# PWR_INP.net
KiCad netlist of a schematic drawn in Altium Designer
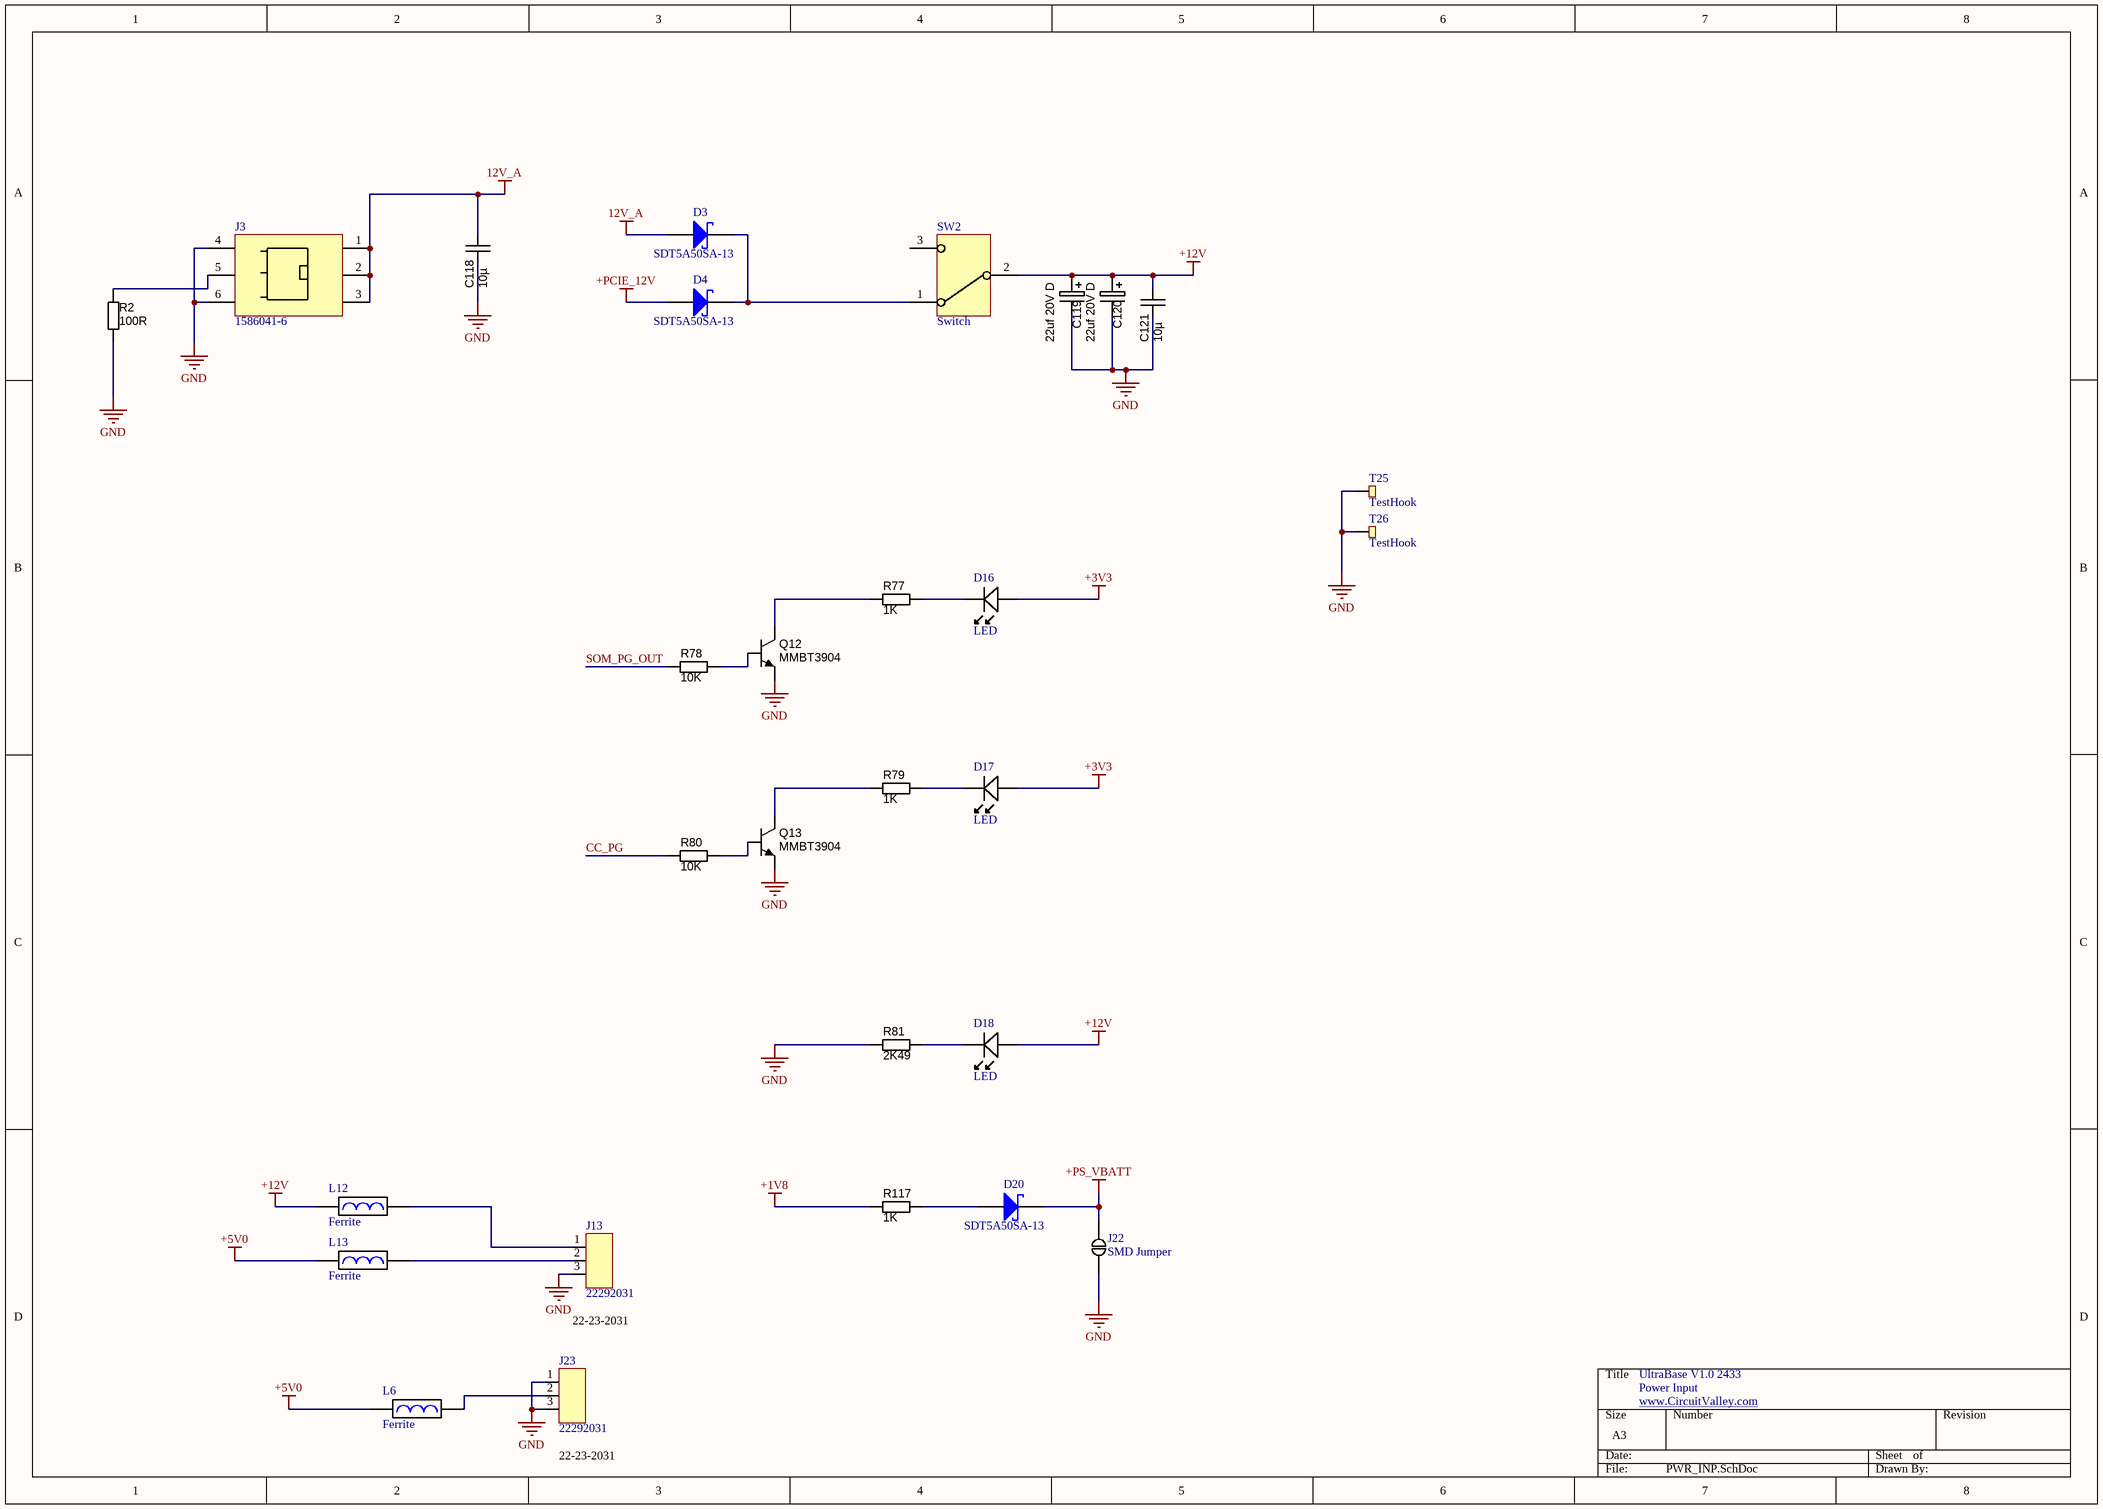
[diagram p0: PWR_INP.SchDoc]

(export (version "E")
  (design (tool "Eeschema 10.0.6"))
  (components
    (comp (ref "C118")
      (value "10µ")
      (footprint "CAPC3225N")
      (description "Capacitor SMD Cer 10uF 20% 16V X5R 1210")
      (fields (field (name "TOLERANCE") "±20%"))
      (libsource (lib "PBL - Capacitors") (part "CAPC_10u_1210_50V"))
    )
    (comp (ref "C119")
      (value "22uf 20V D")
      (footprint "CAPMP7343X310N")
      (description "Capacitor SMD Tant 330uF 20% 6V3 2917")
      (fields
        (field (name "TOLERANCE") "±20%")
        (field (name "MANUFACTURER PART NUMBER") "T520D337M006ATE015")
      )
      (libsource (lib "PBL - Capacitors") (part "CAPT_330u_2917_6V3"))
    )
    (comp (ref "C120")
      (value "22uf 20V D")
      (footprint "CAPMP7343X310N")
      (description "Capacitor SMD Tant 330uF 20% 6V3 2917")
      (fields
        (field (name "TOLERANCE") "±20%")
        (field (name "MANUFACTURER PART NUMBER") "T520D337M006ATE015")
      )
      (libsource (lib "PBL - Capacitors") (part "CAPT_330u_2917_6V3"))
    )
    (comp (ref "C121")
      (value "10µ")
      (footprint "CAPC3225N")
      (description "Capacitor SMD Cer 10uF 20% 16V X5R 1210")
      (fields (field (name "TOLERANCE") "±20%"))
      (libsource (lib "PBL - Capacitors") (part "CAPC_10u_1210_50V"))
    )
    (comp (ref "D3")
      (value "SDT5A50SA-13")
      (footprint "DO-214AC")
      (description "Diode")
      (libsource (lib "cvlib") (part "Diode"))
    )
    (comp (ref "D4")
      (value "SDT5A50SA-13")
      (footprint "DO-214AC")
      (description "Diode")
      (libsource (lib "cvlib") (part "Diode"))
    )
    (comp (ref "D16") (value "LED") (footprint "1206_LED") (libsource (lib "cvlib") (part "LED")))
    (comp (ref "D17") (value "LED") (footprint "1206_LED") (libsource (lib "cvlib") (part "LED")))
    (comp (ref "D18") (value "LED") (footprint "1206_LED") (libsource (lib "cvlib") (part "LED")))
    (comp (ref "D20")
      (value "SDT5A50SA-13")
      (footprint "DO-214AC")
      (description "Diode")
      (libsource (lib "cvlib") (part "Diode"))
    )
    (comp (ref "J3")
      (value "1586041-6")
      (footprint "1586043-6")
      (description "PCIE Molex Power")
      (libsource (lib "cvlib") (part "1586041-6"))
    )
    (comp (ref "J13") (value "22292031") (footprint "22-23-2031") (libsource (lib "cvlib") (part "22292031")))
    (comp (ref "J22")
      (value "SMD Jumper")
      (footprint "SMD_Jumper")
      (libsource (lib "cvlib") (part "SMD_Jumper"))
    )
    (comp (ref "J23") (value "22292031") (footprint "22-23-2031") (libsource (lib "cvlib") (part "22292031")))
    (comp (ref "L6")
      (value "Ferrite")
      (footprint "FBC2012N")
      (description "Ferrite Bead")
      (libsource (lib "cvlib") (part "Ferrite Bead"))
    )
    (comp (ref "L12")
      (value "Ferrite")
      (footprint "FBC2012N")
      (description "Ferrite Bead")
      (libsource (lib "cvlib") (part "Ferrite Bead"))
    )
    (comp (ref "L13")
      (value "Ferrite")
      (footprint "FBC2012N")
      (description "Ferrite Bead")
      (libsource (lib "cvlib") (part "Ferrite Bead"))
    )
    (comp (ref "Q12")
      (value "NPN_MMBT3904")
      (footprint "SOT23-3")
      (description "Transistor SMD NPN 40V 0.2A 350mW SOT-23")
      (fields (field (name "MANUFACTURER PART NUMBER 1") "MMBT3904"))
      (libsource (lib "PBL - Transistors") (part "NPN_MMBT3904"))
    )
    (comp (ref "Q13")
      (value "NPN_MMBT3904")
      (footprint "SOT23-3")
      (description "Transistor SMD NPN 40V 0.2A 350mW SOT-23")
      (fields (field (name "MANUFACTURER PART NUMBER 1") "MMBT3904"))
      (libsource (lib "PBL - Transistors") (part "NPN_MMBT3904"))
    )
    (comp (ref "R2")
      (value "100R")
      (footprint "RESC1608N")
      (description "Resistor, SMD chip")
      (fields (field (name "TOLERANCE") "±5%") (field (name "Comment") "RES_NL_0603"))
      (libsource (lib "") (part "RES_NL_0603_1"))
    )
    (comp (ref "R77")
      (value "1K")
      (footprint "RESC1608N")
      (description "Resistor, SMD chip")
      (fields (field (name "TOLERANCE") "±5%") (field (name "Comment") "RES_NL_0603"))
      (libsource (lib "PBL - Resistors") (part "RES_NL_0603"))
    )
    (comp (ref "R78")
      (value "10K")
      (footprint "RESC1608N")
      (description "Resistor, SMD chip")
      (fields (field (name "TOLERANCE") "±5%") (field (name "Comment") "RES_NL_0603"))
      (libsource (lib "PBL - Resistors") (part "RES_NL_0603"))
    )
    (comp (ref "R79")
      (value "1K")
      (footprint "RESC1608N")
      (description "Resistor, SMD chip")
      (fields (field (name "TOLERANCE") "±5%") (field (name "Comment") "RES_NL_0603"))
      (libsource (lib "PBL - Resistors") (part "RES_NL_0603"))
    )
    (comp (ref "R80")
      (value "10K")
      (footprint "RESC1608N")
      (description "Resistor, SMD chip")
      (fields (field (name "TOLERANCE") "±5%") (field (name "Comment") "RES_NL_0603"))
      (libsource (lib "PBL - Resistors") (part "RES_NL_0603"))
    )
    (comp (ref "R81")
      (value "2K49")
      (footprint "RESC1608N")
      (description "Resistor, SMD chip")
      (fields (field (name "TOLERANCE") "±5%") (field (name "Comment") "RES_NL_0603"))
      (libsource (lib "PBL - Resistors") (part "RES_NL_0603"))
    )
    (comp (ref "R117")
      (value "1K")
      (footprint "RESC1608N")
      (description "Resistor, SMD chip")
      (fields (field (name "TOLERANCE") "±5%") (field (name "Comment") "RES_NL_0603"))
      (libsource (lib "PBL - Resistors") (part "RES_NL_0603"))
    )
    (comp (ref "SW2")
      (value "Switch")
      (footprint "1MS1T1B4M7QES")
      (description "Switch SPDT")
      (libsource (lib "cvlib") (part "Switch_SPDT"))
    )
    (comp (ref "T25") (value "TestHook") (footprint "1502-x") (libsource (lib "cvlib") (part "TestHook")))
    (comp (ref "T26") (value "TestHook") (footprint "1502-x") (libsource (lib "cvlib") (part "TestHook")))
  )
  (nets
    (net (code "1") (name "+1V8") (class "Default")
      (node (ref "R117") (pin "1") (pinfunction "1_1") (pintype "passive"))
    )
    (net (code "2") (name "+3V3") (class "Default")
      (node (ref "D16") (pin "A") (pinfunction "A_A") (pintype "passive"))
      (node (ref "D17") (pin "A") (pinfunction "A_A") (pintype "passive"))
    )
    (net (code "3") (name "+5V0") (class "Default")
      (node (ref "L13") (pin "1") (pinfunction "1_1") (pintype "passive"))
      (node (ref "L6") (pin "1") (pinfunction "1_1") (pintype "passive"))
    )
    (net (code "4") (name "+12V") (class "Default")
      (node (ref "C119") (pin "1") (pintype "passive"))
      (node (ref "C120") (pin "1") (pintype "passive"))
      (node (ref "C121") (pin "1") (pintype "passive"))
      (node (ref "D18") (pin "A") (pinfunction "A_A") (pintype "passive"))
      (node (ref "L12") (pin "1") (pinfunction "1_1") (pintype "passive"))
      (node (ref "SW2") (pin "2") (pintype "passive"))
    )
    (net (code "5") (name "+PCIE_12V") (class "Default")
      (node (ref "D4") (pin "1") (pinfunction "A_1") (pintype "passive"))
    )
    (net (code "6") (name "+PS_VBATT") (class "Default")
      (node (ref "D20") (pin "2") (pinfunction "K_2") (pintype "passive"))
      (node (ref "J22") (pin "2") (pinfunction "2_2") (pintype "passive"))
    )
    (net (code "7") (name "/CC_PG") (class "Default")
      (node (ref "R80") (pin "1") (pinfunction "1_1") (pintype "passive"))
    )
    (net (code "8") (name "/SOM_PG_OUT") (class "Default")
      (node (ref "R78") (pin "1") (pinfunction "1_1") (pintype "passive"))
    )
    (net (code "9") (name "12V_A") (class "Default")
      (node (ref "C118") (pin "1") (pintype "passive"))
      (node (ref "D3") (pin "1") (pinfunction "A_1") (pintype "passive"))
      (node (ref "J3") (pin "1") (pinfunction "IN_1") (pintype "passive"))
      (node (ref "J3") (pin "2") (pinfunction "IN_2") (pintype "passive"))
      (node (ref "J3") (pin "3") (pinfunction "IN_3") (pintype "passive"))
    )
    (net (code "10") (name "GND") (class "Default")
      (node (ref "C118") (pin "2") (pintype "passive"))
      (node (ref "C119") (pin "2") (pintype "passive"))
      (node (ref "C120") (pin "2") (pintype "passive"))
      (node (ref "C121") (pin "2") (pintype "passive"))
      (node (ref "J13") (pin "3") (pintype "passive"))
      (node (ref "J22") (pin "1") (pinfunction "1_1") (pintype "passive"))
      (node (ref "J23") (pin "1") (pintype "passive"))
      (node (ref "J23") (pin "3") (pintype "passive"))
      (node (ref "J3") (pin "4") (pinfunction "IN_4") (pintype "passive"))
      (node (ref "J3") (pin "6") (pinfunction "6_6") (pintype "passive"))
      (node (ref "Q12") (pin "2") (pinfunction "E_2") (pintype "passive"))
      (node (ref "Q13") (pin "2") (pinfunction "E_2") (pintype "passive"))
      (node (ref "R2") (pin "2") (pinfunction "2_2") (pintype "passive"))
      (node (ref "R81") (pin "1") (pinfunction "1_1") (pintype "passive"))
      (node (ref "T25") (pin "1") (pinfunction "TP_1") (pintype "power_in"))
      (node (ref "T26") (pin "1") (pinfunction "TP_1") (pintype "power_in"))
    )
    (net (code "11") (name "Net-(D3-K)") (class "Default")
      (node (ref "D3") (pin "2") (pinfunction "K_2") (pintype "passive"))
      (node (ref "D4") (pin "2") (pinfunction "K_2") (pintype "passive"))
      (node (ref "SW2") (pin "1") (pintype "passive"))
    )
    (net (code "12") (name "Net-(D16-PadK)") (class "Default")
      (node (ref "D16") (pin "K") (pinfunction "K_K") (pintype "passive"))
      (node (ref "R77") (pin "2") (pinfunction "2_2") (pintype "passive"))
    )
    (net (code "13") (name "Net-(D17-PadK)") (class "Default")
      (node (ref "D17") (pin "K") (pinfunction "K_K") (pintype "passive"))
      (node (ref "R79") (pin "2") (pinfunction "2_2") (pintype "passive"))
    )
    (net (code "14") (name "Net-(D18-PadK)") (class "Default")
      (node (ref "D18") (pin "K") (pinfunction "K_K") (pintype "passive"))
      (node (ref "R81") (pin "2") (pinfunction "2_2") (pintype "passive"))
    )
    (net (code "15") (name "Net-(D20-A)") (class "Default")
      (node (ref "D20") (pin "1") (pinfunction "A_1") (pintype "passive"))
      (node (ref "R117") (pin "2") (pinfunction "2_2") (pintype "passive"))
    )
    (net (code "16") (name "Net-(J3-Pad5)") (class "Default")
      (node (ref "J3") (pin "5") (pinfunction "5_5") (pintype "passive"))
      (node (ref "R2") (pin "1") (pinfunction "1_1") (pintype "passive"))
    )
    (net (code "17") (name "Net-(J13-Pad1)") (class "Default")
      (node (ref "J13") (pin "1") (pintype "passive"))
      (node (ref "L12") (pin "2") (pinfunction "2_2") (pintype "passive"))
    )
    (net (code "18") (name "Net-(J13-Pad2)") (class "Default")
      (node (ref "J13") (pin "2") (pintype "passive"))
      (node (ref "L13") (pin "2") (pinfunction "2_2") (pintype "passive"))
    )
    (net (code "19") (name "Net-(J23-Pad2)") (class "Default")
      (node (ref "J23") (pin "2") (pintype "passive"))
      (node (ref "L6") (pin "2") (pinfunction "2_2") (pintype "passive"))
    )
    (net (code "20") (name "Net-(Q12-B)") (class "Default")
      (node (ref "Q12") (pin "1") (pinfunction "B_1") (pintype "passive"))
      (node (ref "R78") (pin "2") (pinfunction "2_2") (pintype "passive"))
    )
    (net (code "21") (name "Net-(Q12-C)") (class "Default")
      (node (ref "Q12") (pin "3") (pinfunction "C_3") (pintype "passive"))
      (node (ref "R77") (pin "1") (pinfunction "1_1") (pintype "passive"))
    )
    (net (code "22") (name "Net-(Q13-B)") (class "Default")
      (node (ref "Q13") (pin "1") (pinfunction "B_1") (pintype "passive"))
      (node (ref "R80") (pin "2") (pinfunction "2_2") (pintype "passive"))
    )
    (net (code "23") (name "Net-(Q13-C)") (class "Default")
      (node (ref "Q13") (pin "3") (pinfunction "C_3") (pintype "passive"))
      (node (ref "R79") (pin "1") (pinfunction "1_1") (pintype "passive"))
    )
    (net (code "24") (name "unconnected-(SW2-Pad3)") (class "Default")
      (node (ref "SW2") (pin "3") (pintype "passive"))
    )
  )
)
